# RcTransmitterPower.net
KiCad netlist of a schematic drawn in Altium Designer
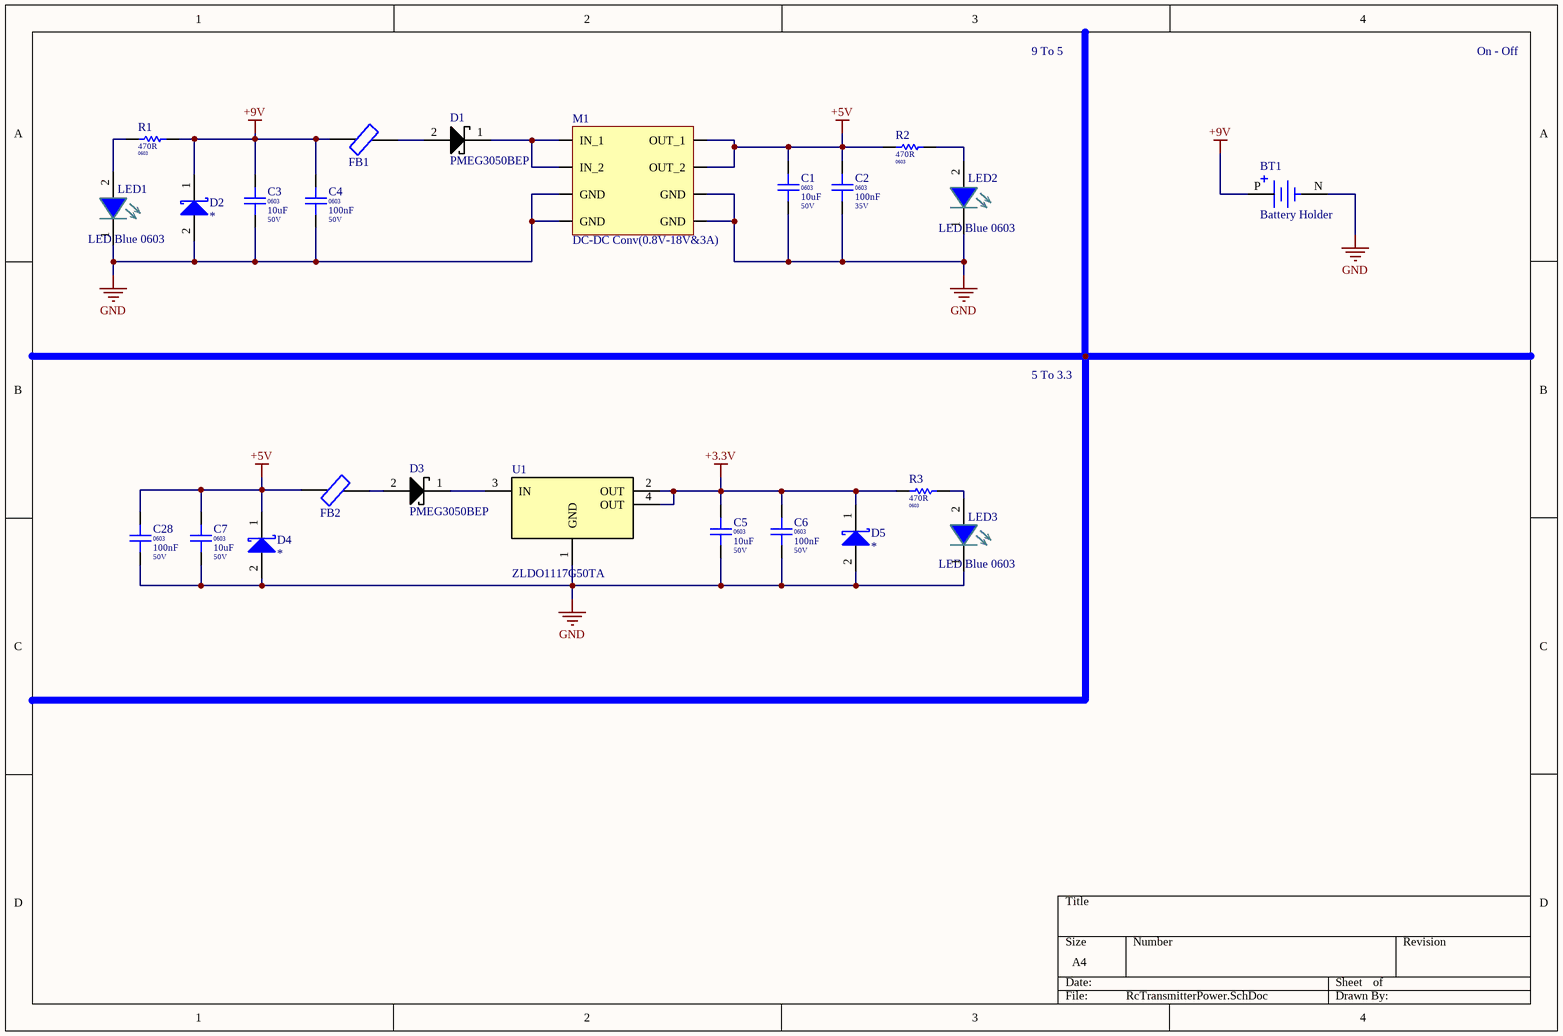
[diagram p0: RcTransmitterPower.SchDoc]

(export (version "E")
  (design (tool "Eeschema 10.0.6"))
  (components
    (comp (ref "BT1")
      (value "Battery Holder")
      (footprint "BAT_BC9VPC")
      (description "BATTERY HOLDER 9V PC PIN")
      (fields (field (name "MF") "MPD") (field (name "MP") "BC9VPC"))
      (libsource (lib "RcTransmitterSchlib1") (part "Battery Holder"))
    )
    (comp (ref "C1")
      (value "10uF")
      (footprint "CAPC 0603")
      (description "Capacitor Ceramic 10uF 50V 0603")
      (fields
        (field (name "TOLERANCE") "%10")
        (field (name "PACKAGE / CASE") "0603")
        (field (name "VOLTAGE") "50V")
        (field (name "PART NUMBER") "CAPC0301")
      )
      (libsource (lib "AESK Database Library") (part "NPCapacitor"))
    )
    (comp (ref "C2")
      (value "100nF")
      (footprint "CAPC 0603")
      (description "Capacitor Ceramic 100nF 35V 0603")
      (fields
        (field (name "TOLERANCE") "%10")
        (field (name "PACKAGE / CASE") "0603")
        (field (name "VOLTAGE") "35V")
        (field (name "PART NUMBER") "CAPC0328")
      )
      (libsource (lib "AESK Database Library") (part "NPCapacitor"))
    )
    (comp (ref "C3")
      (value "10uF")
      (footprint "CAPC 0603")
      (description "Capacitor Ceramic 10uF 50V 0603")
      (fields
        (field (name "TOLERANCE") "%10")
        (field (name "PACKAGE / CASE") "0603")
        (field (name "VOLTAGE") "50V")
        (field (name "PART NUMBER") "CAPC0301")
      )
      (libsource (lib "AESK Database Library") (part "NPCapacitor"))
    )
    (comp (ref "C4")
      (value "100nF")
      (footprint "CAPC 0603")
      (description "Capacitor Ceramic 100nF 50V 0603")
      (fields
        (field (name "TOLERANCE") "%10")
        (field (name "PACKAGE / CASE") "0603")
        (field (name "VOLTAGE") "50V")
        (field (name "PART NUMBER") "CAPC0285")
      )
      (libsource (lib "AESK Database Library") (part "NPCapacitor"))
    )
    (comp (ref "C5")
      (value "10uF")
      (footprint "CAPC 0603")
      (description "Capacitor Ceramic 10uF 50V 0603")
      (fields
        (field (name "TOLERANCE") "%10")
        (field (name "PACKAGE / CASE") "0603")
        (field (name "VOLTAGE") "50V")
        (field (name "PART NUMBER") "CAPC0301")
      )
      (libsource (lib "AESK Database Library") (part "NPCapacitor"))
    )
    (comp (ref "C6")
      (value "100nF")
      (footprint "CAPC 0603")
      (description "Capacitor Ceramic 100nF 50V 0603")
      (fields
        (field (name "TOLERANCE") "%10")
        (field (name "PACKAGE / CASE") "0603")
        (field (name "VOLTAGE") "50V")
        (field (name "PART NUMBER") "CAPC0285")
      )
      (libsource (lib "AESK Database Library") (part "NPCapacitor"))
    )
    (comp (ref "C7")
      (value "10uF")
      (footprint "CAPC 0603")
      (description "Capacitor Ceramic 10uF 50V 0603")
      (fields
        (field (name "TOLERANCE") "%10")
        (field (name "PACKAGE / CASE") "0603")
        (field (name "VOLTAGE") "50V")
        (field (name "PART NUMBER") "CAPC0301")
      )
      (libsource (lib "AESK Database Library") (part "NPCapacitor"))
    )
    (comp (ref "C28")
      (value "100nF")
      (footprint "CAPC 0603")
      (description "Capacitor Ceramic 100nF 50V 0603")
      (fields
        (field (name "TOLERANCE") "%10")
        (field (name "PACKAGE / CASE") "0603")
        (field (name "VOLTAGE") "50V")
        (field (name "PART NUMBER") "CAPC0285")
      )
      (libsource (lib "AESK Database Library") (part "NPCapacitor"))
    )
    (comp (ref "D1")
      (value "PMEG3050BEP")
      (footprint "SOD470X100-2N")
      (description "Schotky Diode")
      (fields
        (field (name "MANUFACTURER") "Nexperia USA")
        (field (name "MANUFACTURER PART NUMBER") "PMEG3050BEP,115")
      )
      (libsource (lib "RcTransmitterSchlib1") (part "Schotky Diode"))
    )
    (comp (ref "D2")
      (value "*")
      (footprint "DO-214AC, SMA")
      (fields (field (name "PART NUMBER") "Diode0012"))
      (libsource (lib "AESK Database Library") (part "Schottky Diode"))
    )
    (comp (ref "D3")
      (value "PMEG3050BEP")
      (footprint "SOD470X100-2N")
      (description "Schotky Diode")
      (fields
        (field (name "MANUFACTURER") "Nexperia USA")
        (field (name "MANUFACTURER PART NUMBER") "PMEG3050BEP,115")
      )
      (libsource (lib "RcTransmitterSchlib1") (part "Schotky Diode"))
    )
    (comp (ref "D4")
      (value "*")
      (footprint "DO-214AC, SMA")
      (fields (field (name "PART NUMBER") "Diode0012"))
      (libsource (lib "AESK Database Library") (part "Schottky Diode"))
    )
    (comp (ref "D5")
      (value "*")
      (footprint "DO-214AC, SMA")
      (fields (field (name "PART NUMBER") "Diode0012"))
      (libsource (lib "AESK Database Library") (part "Schottky Diode"))
    )
    (comp (ref "FB1")
      (value "Ferrite Bead")
      (footprint "FCM1608KF-601T03")
      (libsource (lib "RcTransmitterSchlib1") (part "FCM1608KF-601T03"))
    )
    (comp (ref "FB2")
      (value "Ferrite Bead")
      (footprint "FCM1608KF-601T03")
      (libsource (lib "RcTransmitterSchlib1") (part "FCM1608KF-601T03"))
    )
    (comp (ref "LED1")
      (value "LED Blue 0603")
      (footprint "LED BLUE 0603")
      (libsource (lib "RcTransmitterSchlib1") (part "LED Blue 0603"))
    )
    (comp (ref "LED2")
      (value "LED Blue 0603")
      (footprint "LED BLUE 0603")
      (libsource (lib "RcTransmitterSchlib1") (part "LED Blue 0603"))
    )
    (comp (ref "LED3")
      (value "LED Blue 0603")
      (footprint "LED BLUE 0603")
      (libsource (lib "RcTransmitterSchlib1") (part "LED Blue 0603"))
    )
    (comp (ref "M1")
      (value "DC-DC Conv(0.8V-18V&3A)")
      (footprint "mp")
      (libsource (lib "RcTransmitterSchlib1") (part "MP1584EN"))
    )
    (comp (ref "R1")
      (value "470R")
      (footprint "RESC 0603")
      (description "470R 0603")
      (fields
        (field (name "TOLERANCE") "%5")
        (field (name "POWER") "1/10W")
        (field (name "PACKAGE / CASE") "0603")
      )
      (libsource (lib "AESK Database Library") (part "Resistor"))
    )
    (comp (ref "R2")
      (value "470R")
      (footprint "RESC 0603")
      (description "470R 0603")
      (fields
        (field (name "TOLERANCE") "%5")
        (field (name "POWER") "1/10W")
        (field (name "PACKAGE / CASE") "0603")
      )
      (libsource (lib "AESK Database Library") (part "Resistor"))
    )
    (comp (ref "R3")
      (value "470R")
      (footprint "RESC 0603")
      (description "470R 0603")
      (fields
        (field (name "TOLERANCE") "%5")
        (field (name "POWER") "1/10W")
        (field (name "PACKAGE / CASE") "0603")
      )
      (libsource (lib "AESK Database Library") (part "Resistor"))
    )
    (comp (ref "U1")
      (value "ZLDO1117G50TA")
      (footprint "1117")
      (description "IC REG LDO 5V 1A SOT223")
      (libsource (lib "RcTransmitterSchlib1") (part "ZLDO1117G50TA"))
    )
  )
  (nets
    (net (code "1") (name "+3.3V") (class "Default")
      (node (ref "C5") (pin "2") (pinfunction "2_2") (pintype "passive"))
      (node (ref "C6") (pin "2") (pinfunction "2_2") (pintype "passive"))
      (node (ref "D5") (pin "1") (pinfunction "K_1") (pintype "passive"))
      (node (ref "R3") (pin "2") (pinfunction "2_2") (pintype "passive"))
      (node (ref "U1") (pin "2") (pinfunction "OUT_2") (pintype "power_in"))
      (node (ref "U1") (pin "4") (pinfunction "OUT_4") (pintype "power_in"))
    )
    (net (code "2") (name "+5V") (class "Default")
      (node (ref "C1") (pin "2") (pinfunction "2_2") (pintype "passive"))
      (node (ref "C2") (pin "2") (pinfunction "2_2") (pintype "passive"))
      (node (ref "C28") (pin "2") (pinfunction "2_2") (pintype "passive"))
      (node (ref "C7") (pin "2") (pinfunction "2_2") (pintype "passive"))
      (node (ref "D4") (pin "1") (pinfunction "K_1") (pintype "passive"))
      (node (ref "FB2") (pin "1") (pinfunction "1_1") (pintype "passive"))
      (node (ref "M1") (pin "3") (pinfunction "OUT_1_3") (pintype "passive"))
      (node (ref "M1") (pin "4") (pinfunction "OUT_2_4") (pintype "passive"))
      (node (ref "R2") (pin "2") (pinfunction "2_2") (pintype "passive"))
    )
    (net (code "3") (name "+9V") (class "Default")
      (node (ref "BT1") (pin "P") (pinfunction "POS_P") (pintype "passive"))
      (node (ref "C3") (pin "2") (pinfunction "2_2") (pintype "passive"))
      (node (ref "C4") (pin "2") (pinfunction "2_2") (pintype "passive"))
      (node (ref "D2") (pin "1") (pinfunction "K_1") (pintype "passive"))
      (node (ref "FB1") (pin "1") (pinfunction "1_1") (pintype "passive"))
      (node (ref "R1") (pin "1") (pinfunction "1_1") (pintype "passive"))
    )
    (net (code "4") (name "GND") (class "Default")
      (node (ref "BT1") (pin "N") (pinfunction "NEG_N") (pintype "passive"))
      (node (ref "C1") (pin "1") (pinfunction "1_1") (pintype "passive"))
      (node (ref "C2") (pin "1") (pinfunction "1_1") (pintype "passive"))
      (node (ref "C28") (pin "1") (pinfunction "1_1") (pintype "passive"))
      (node (ref "C3") (pin "1") (pinfunction "1_1") (pintype "passive"))
      (node (ref "C4") (pin "1") (pinfunction "1_1") (pintype "passive"))
      (node (ref "C5") (pin "1") (pinfunction "1_1") (pintype "passive"))
      (node (ref "C6") (pin "1") (pinfunction "1_1") (pintype "passive"))
      (node (ref "C7") (pin "1") (pinfunction "1_1") (pintype "passive"))
      (node (ref "D2") (pin "2") (pinfunction "A_2") (pintype "passive"))
      (node (ref "D4") (pin "2") (pinfunction "A_2") (pintype "passive"))
      (node (ref "D5") (pin "2") (pinfunction "A_2") (pintype "passive"))
      (node (ref "LED1") (pin "1") (pintype "passive"))
      (node (ref "LED2") (pin "1") (pintype "passive"))
      (node (ref "LED3") (pin "1") (pintype "passive"))
      (node (ref "M1") (pin "5") (pinfunction "GND_5") (pintype "passive"))
      (node (ref "M1") (pin "6") (pinfunction "GND_6") (pintype "passive"))
      (node (ref "M1") (pin "7") (pinfunction "GND_7") (pintype "passive"))
      (node (ref "M1") (pin "8") (pinfunction "GND_8") (pintype "passive"))
      (node (ref "U1") (pin "1") (pinfunction "GND_1") (pintype "power_in"))
    )
    (net (code "5") (name "Net-(D1-A)") (class "Default")
      (node (ref "D1") (pin "2") (pinfunction "A_2") (pintype "passive"))
      (node (ref "FB1") (pin "2") (pinfunction "2_2") (pintype "passive"))
    )
    (net (code "6") (name "Net-(D1-K)") (class "Default")
      (node (ref "D1") (pin "1") (pinfunction "K_1") (pintype "passive"))
      (node (ref "M1") (pin "1") (pinfunction "IN_1_1") (pintype "passive"))
      (node (ref "M1") (pin "2") (pinfunction "IN_2_2") (pintype "passive"))
    )
    (net (code "7") (name "Net-(D3-A)") (class "Default")
      (node (ref "D3") (pin "2") (pinfunction "A_2") (pintype "passive"))
      (node (ref "FB2") (pin "2") (pinfunction "2_2") (pintype "passive"))
    )
    (net (code "8") (name "Net-(D3-K)") (class "Default")
      (node (ref "D3") (pin "1") (pinfunction "K_1") (pintype "passive"))
      (node (ref "U1") (pin "3") (pinfunction "IN_3") (pintype "power_in"))
    )
    (net (code "9") (name "Net-(LED1-Pad2)") (class "Default")
      (node (ref "LED1") (pin "2") (pintype "passive"))
      (node (ref "R1") (pin "2") (pinfunction "2_2") (pintype "passive"))
    )
    (net (code "10") (name "Net-(LED2-Pad2)") (class "Default")
      (node (ref "LED2") (pin "2") (pintype "passive"))
      (node (ref "R2") (pin "1") (pinfunction "1_1") (pintype "passive"))
    )
    (net (code "11") (name "Net-(LED3-Pad2)") (class "Default")
      (node (ref "LED3") (pin "2") (pintype "passive"))
      (node (ref "R3") (pin "1") (pinfunction "1_1") (pintype "passive"))
    )
  )
)
